# 05_-_CPU_-_PCIE_SATA.net
KiCad netlist of a schematic drawn in Altium Designer
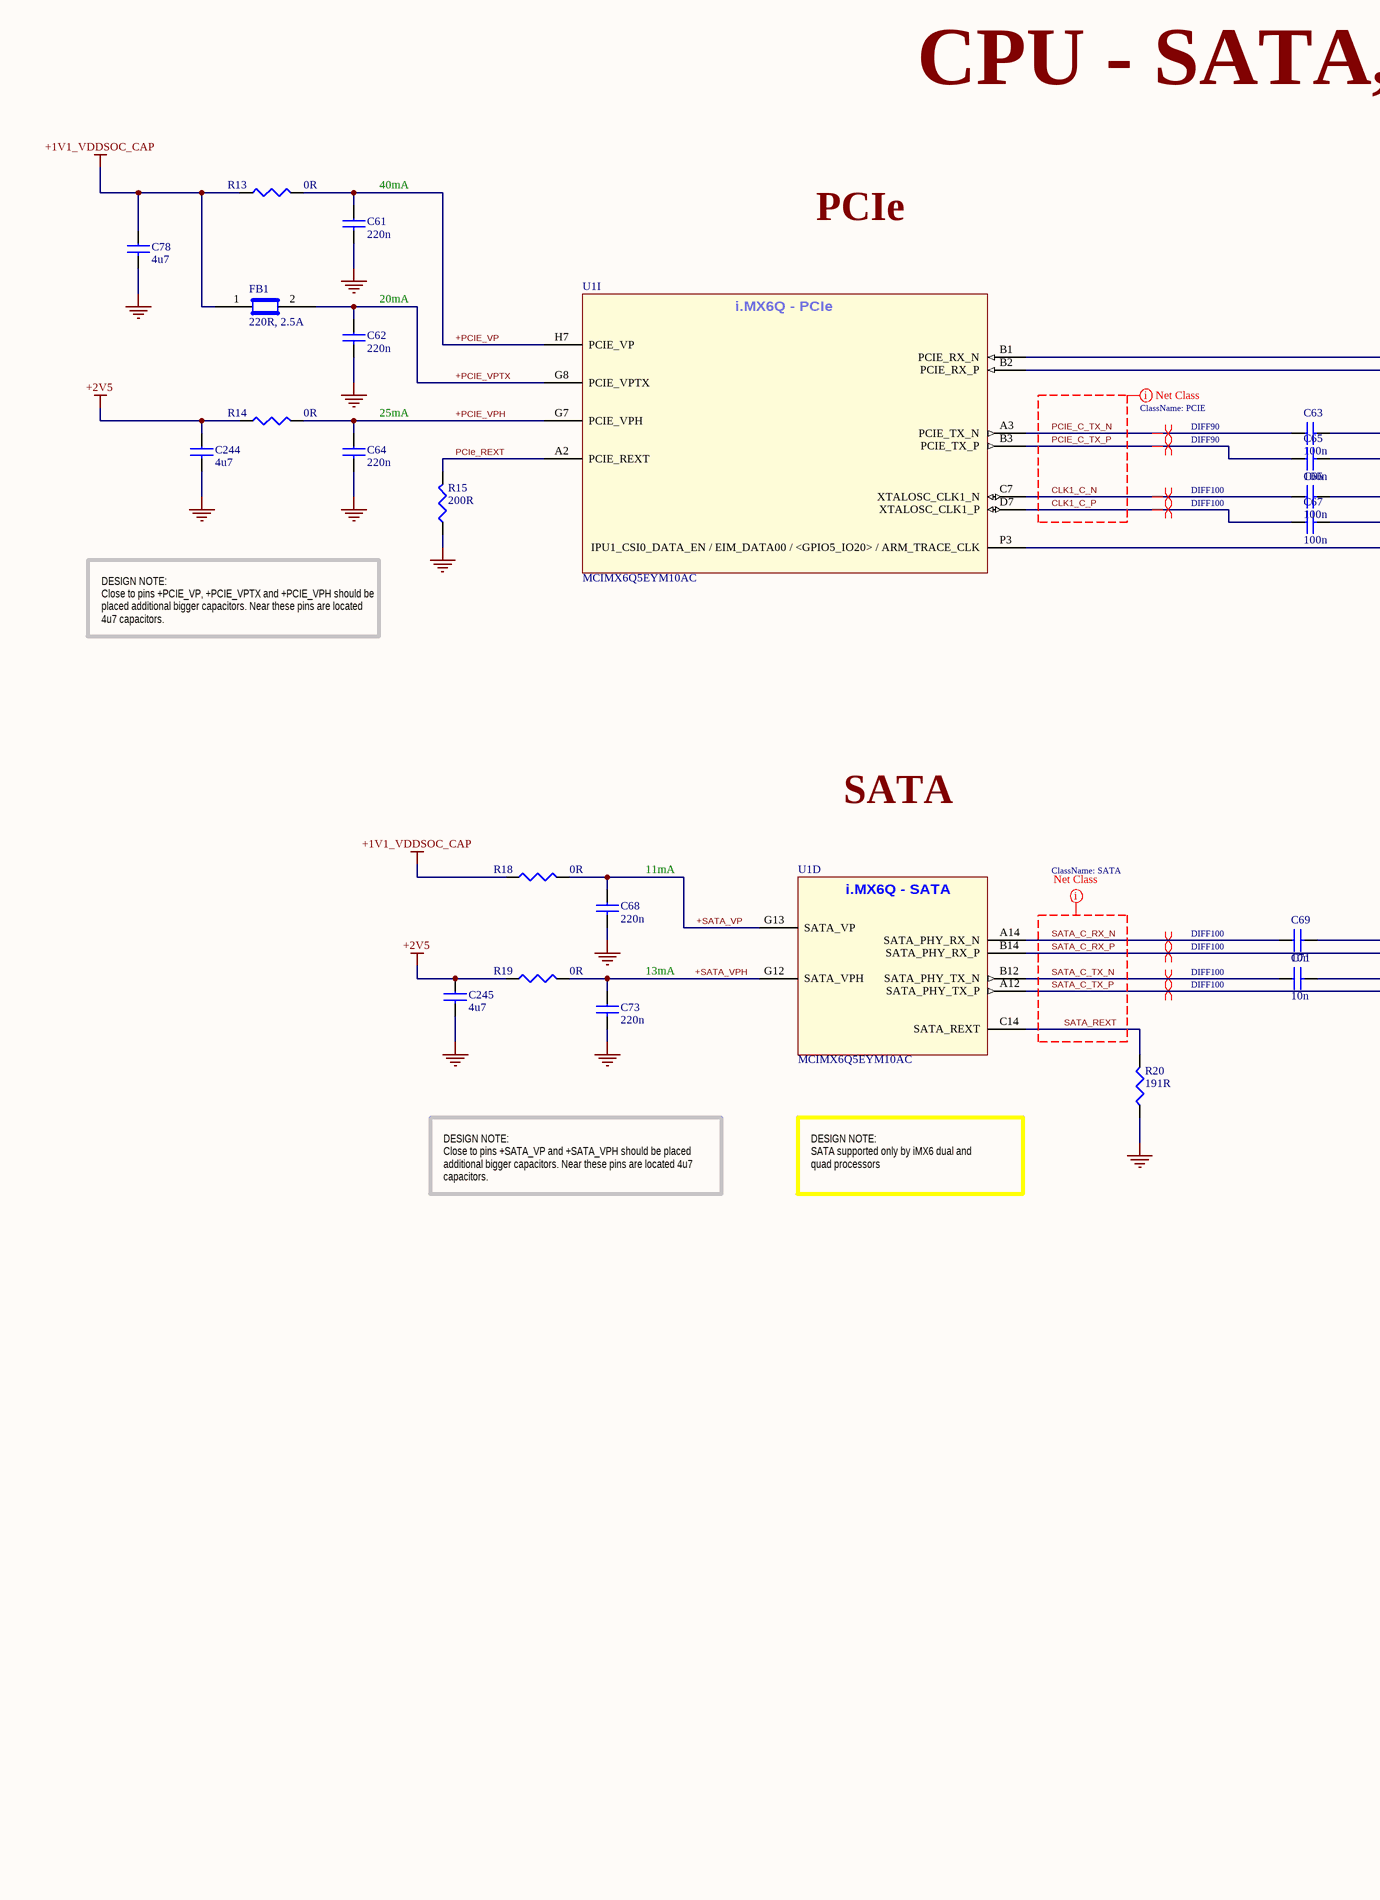
[diagram p0: [05] - CPU - PCIE, SATA.SchDoc, left]
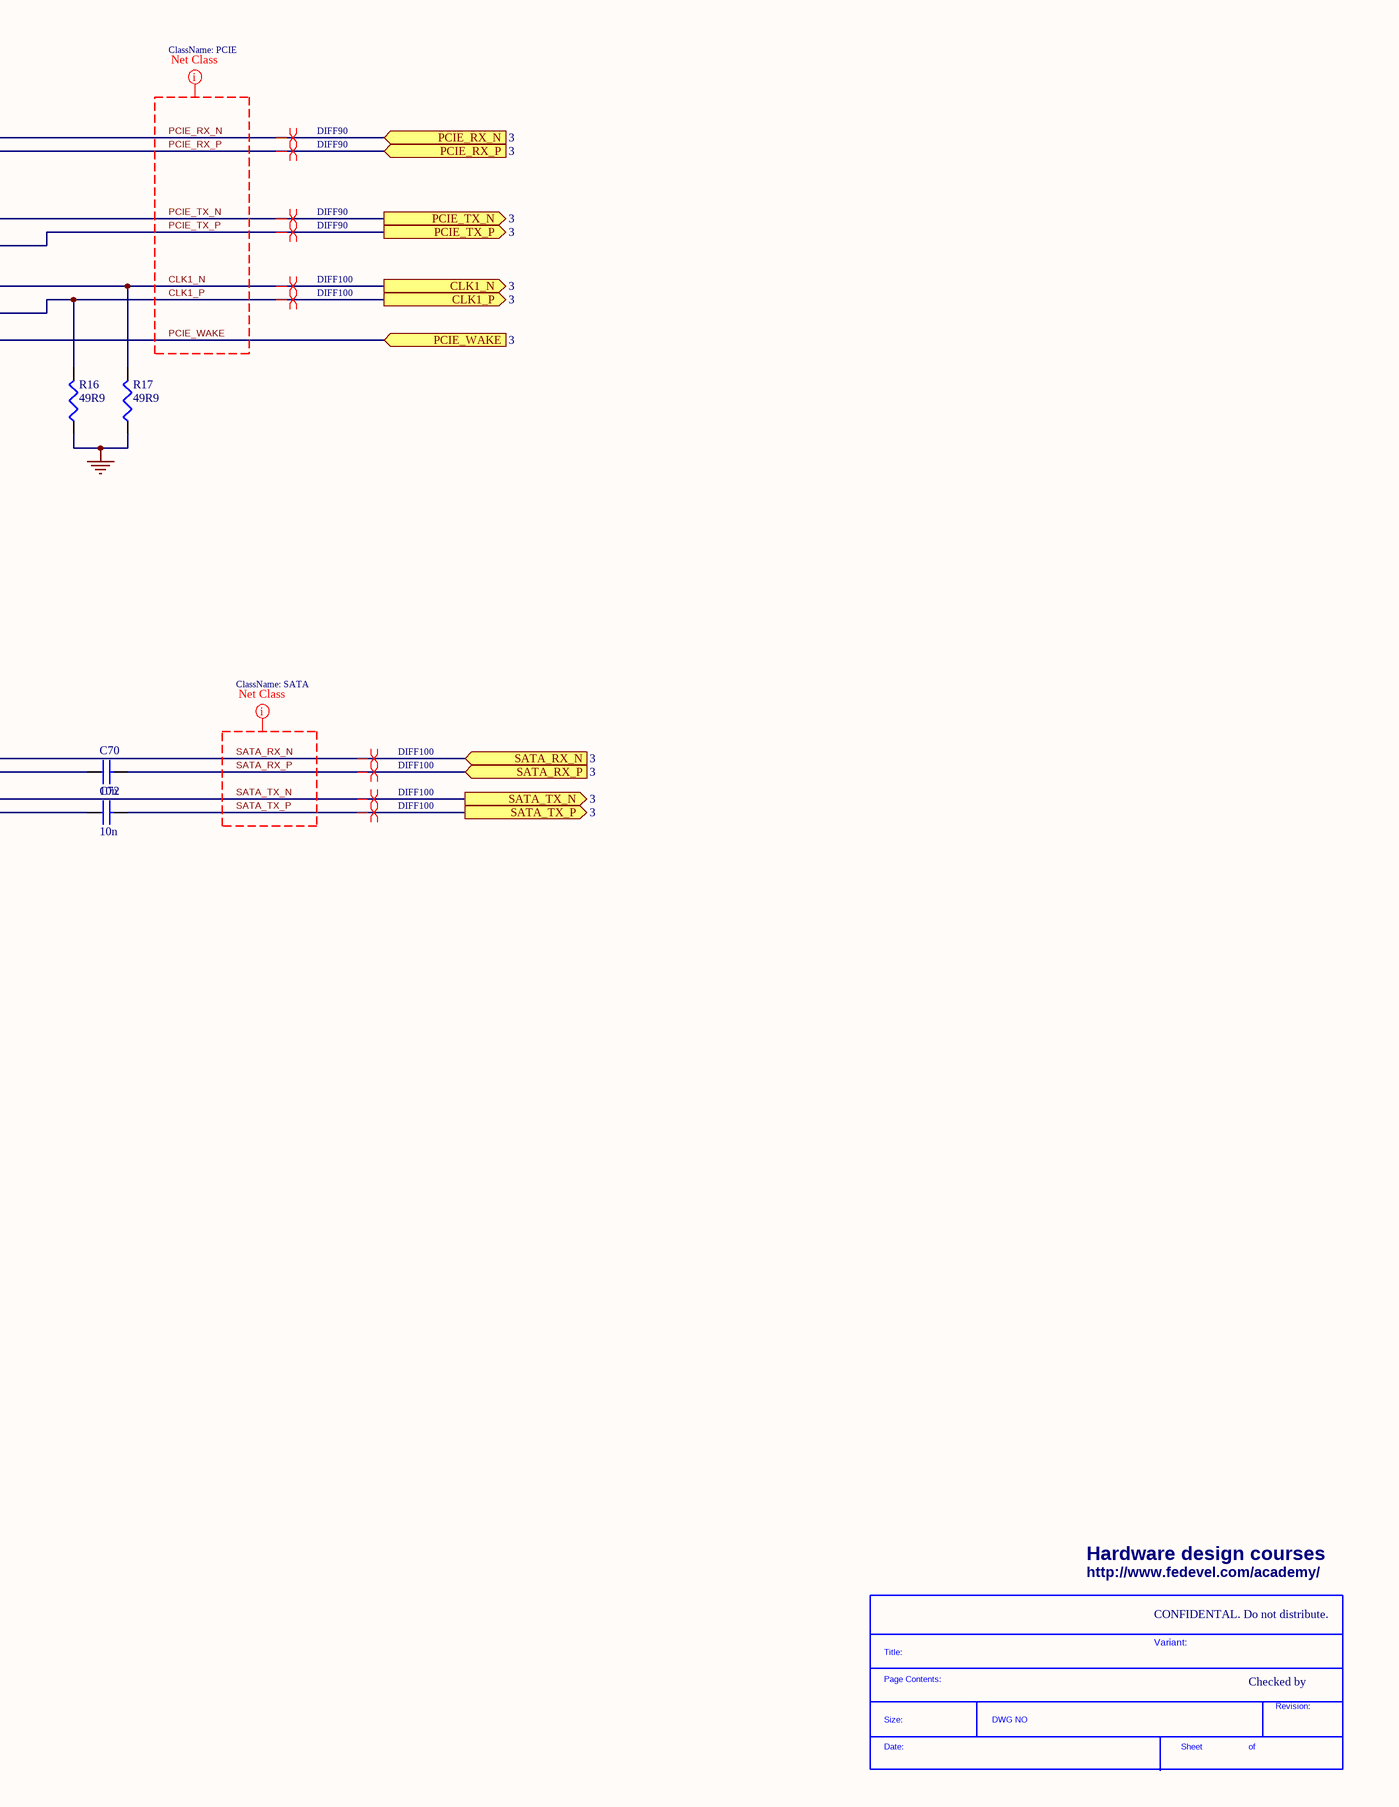
[diagram p1: [05] - CPU - PCIE, SATA.SchDoc, right]

(export (version "E")
  (design (tool "Eeschema 10.0.6"))
  (components
    (comp (ref "C61")
      (value "220n")
      (footprint "C0402")
      (description "CAP CER .22UF 25V X5R 20% 0402")
      (fields
        (field (name "MANUFACTURER") "TDK Corporation")
        (field (name "MANUFACTURER PART NUMBER") "C1005X5R1E224M")
      )
      (libsource (lib "iMX6 Rex_V1I1") (part "C1005X5R1E224M"))
    )
    (comp (ref "C62")
      (value "220n")
      (footprint "C0402")
      (description "CAP CER .22UF 25V X5R 20% 0402")
      (fields
        (field (name "MANUFACTURER") "TDK Corporation")
        (field (name "MANUFACTURER PART NUMBER") "C1005X5R1E224M")
      )
      (libsource (lib "iMX6 Rex_V1I1") (part "C1005X5R1E224M"))
    )
    (comp (ref "C63")
      (value "100n")
      (footprint "C0402")
      (description "CAP CER .10UF 50V X5R 10% 0402")
      (fields
        (field (name "MANUFACTURER") "TDK Corporation")
        (field (name "MANUFACTURER PART NUMBER") "C1005X5R1H104K")
      )
      (libsource (lib "iMX6 Rex_V1I1") (part "C1005X5R1H104K"))
    )
    (comp (ref "C64")
      (value "220n")
      (footprint "C0402")
      (description "CAP CER .22UF 25V X5R 20% 0402")
      (fields
        (field (name "MANUFACTURER") "TDK Corporation")
        (field (name "MANUFACTURER PART NUMBER") "C1005X5R1E224M")
      )
      (libsource (lib "iMX6 Rex_V1I1") (part "C1005X5R1E224M"))
    )
    (comp (ref "C65")
      (value "100n")
      (footprint "C0402")
      (description "CAP CER .10UF 50V X5R 10% 0402")
      (fields
        (field (name "MANUFACTURER") "TDK Corporation")
        (field (name "MANUFACTURER PART NUMBER") "C1005X5R1H104K")
      )
      (libsource (lib "iMX6 Rex_V1I1") (part "C1005X5R1H104K"))
    )
    (comp (ref "C66")
      (value "100n")
      (footprint "C0402")
      (description "CAP CER .10UF 50V X5R 10% 0402")
      (fields
        (field (name "MANUFACTURER") "TDK Corporation")
        (field (name "MANUFACTURER PART NUMBER") "C1005X5R1H104K")
      )
      (libsource (lib "iMX6 Rex_V1I1") (part "C1005X5R1H104K"))
    )
    (comp (ref "C67")
      (value "100n")
      (footprint "C0402")
      (description "CAP CER .10UF 50V X5R 10% 0402")
      (fields
        (field (name "MANUFACTURER") "TDK Corporation")
        (field (name "MANUFACTURER PART NUMBER") "C1005X5R1H104K")
      )
      (libsource (lib "iMX6 Rex_V1I1") (part "C1005X5R1H104K"))
    )
    (comp (ref "C68")
      (value "220n")
      (footprint "C0402")
      (description "CAP CER .22UF 25V X5R 20% 0402")
      (fields
        (field (name "MANUFACTURER") "TDK Corporation")
        (field (name "MANUFACTURER PART NUMBER") "C1005X5R1E224M")
      )
      (libsource (lib "iMX6 Rex_V1I1") (part "C1005X5R1E224M"))
    )
    (comp (ref "C69")
      (value "10n")
      (footprint "C0402")
      (description "CAP CER 10000PF 16V X7R 10% 0402")
      (fields
        (field (name "MANUFACTURER") "TDK Corporation")
        (field (name "MANUFACTURER PART NUMBER") "C1005X7R1C103K")
      )
      (libsource (lib "iMX6 Rex_V1I1") (part "C1005X7R1C103K"))
    )
    (comp (ref "C70")
      (value "10n")
      (footprint "C0402")
      (description "CAP CER 10000PF 16V X7R 10% 0402")
      (fields
        (field (name "MANUFACTURER") "TDK Corporation")
        (field (name "MANUFACTURER PART NUMBER") "C1005X7R1C103K")
      )
      (libsource (lib "iMX6 Rex_V1I1") (part "C1005X7R1C103K"))
    )
    (comp (ref "C71")
      (value "10n")
      (footprint "C0402")
      (description "CAP CER 10000PF 16V X7R 10% 0402")
      (fields
        (field (name "MANUFACTURER") "TDK Corporation")
        (field (name "MANUFACTURER PART NUMBER") "C1005X7R1C103K")
      )
      (libsource (lib "iMX6 Rex_V1I1") (part "C1005X7R1C103K"))
    )
    (comp (ref "C72")
      (value "10n")
      (footprint "C0402")
      (description "CAP CER 10000PF 16V X7R 10% 0402")
      (fields
        (field (name "MANUFACTURER") "TDK Corporation")
        (field (name "MANUFACTURER PART NUMBER") "C1005X7R1C103K")
      )
      (libsource (lib "iMX6 Rex_V1I1") (part "C1005X7R1C103K"))
    )
    (comp (ref "C73")
      (value "220n")
      (footprint "C0402")
      (description "CAP CER .22UF 25V X5R 20% 0402")
      (fields
        (field (name "MANUFACTURER") "TDK Corporation")
        (field (name "MANUFACTURER PART NUMBER") "C1005X5R1E224M")
      )
      (libsource (lib "iMX6 Rex_V1I1") (part "C1005X5R1E224M"))
    )
    (comp (ref "C78")
      (value "4u7")
      (footprint "C0402")
      (description "CAP CER 4.7UF 10V 20% X5R 0402")
      (fields
        (field (name "MANUFACTURER") "TDK Corporation")
        (field (name "MANUFACTURER PART NUMBER") "C1005X5R1A475M")
        (field (name ".CHECKED PCB") "RF")
        (field (name ".CHECKED SCH") "RF")
      )
      (libsource (lib "iMX6 Rex_V1I1") (part "C1005X5R1A475M"))
    )
    (comp (ref "C244")
      (value "4u7")
      (footprint "C0402")
      (description "CAP CER 4.7UF 10V 20% X5R 0402")
      (fields
        (field (name "MANUFACTURER") "TDK Corporation")
        (field (name "MANUFACTURER PART NUMBER") "C1005X5R1A475M")
        (field (name ".CHECKED PCB") "RF")
        (field (name ".CHECKED SCH") "RF")
      )
      (libsource (lib "iMX6 Rex_V1I1") (part "C1005X5R1A475M"))
    )
    (comp (ref "C245")
      (value "4u7")
      (footprint "C0402")
      (description "CAP CER 4.7UF 10V 20% X5R 0402")
      (fields
        (field (name "MANUFACTURER") "TDK Corporation")
        (field (name "MANUFACTURER PART NUMBER") "C1005X5R1A475M")
        (field (name ".CHECKED PCB") "RF")
        (field (name ".CHECKED SCH") "RF")
      )
      (libsource (lib "iMX6 Rex_V1I1") (part "C1005X5R1A475M"))
    )
    (comp (ref "FB1")
      (value "220R, 2.5A")
      (footprint "C0603")
      (description "FERRITE CHIP 220 OHM 2500MA 0603")
      (fields
        (field (name "MANUFACTURER") "Murata Electronics North America")
        (field (name "MANUFACTURER PART NUMBER") "BLM18SG221TN1D")
        (field (name ".CHECKED PCB") "RF")
        (field (name ".CHECKED SCH") "RF")
      )
      (libsource (lib "iMX6 Rex_V1I1") (part "BLM18SG221TN1D"))
    )
    (comp (ref "R13")
      (value "0R")
      (footprint "R0402")
      (description "RES 0.0 OHM 1/16W 0402 SMD")
      (fields
        (field (name "MANUFACTURER") "Yageo")
        (field (name "MANUFACTURER PART NUMBER") "RC0402JR-070RL")
      )
      (libsource (lib "iMX6 Rex_V1I1") (part "RC0402JR-070RL"))
    )
    (comp (ref "R14")
      (value "0R")
      (footprint "R0402")
      (description "RES 0.0 OHM 1/16W 0402 SMD")
      (fields
        (field (name "MANUFACTURER") "Yageo")
        (field (name "MANUFACTURER PART NUMBER") "RC0402JR-070RL")
      )
      (libsource (lib "iMX6 Rex_V1I1") (part "RC0402JR-070RL"))
    )
    (comp (ref "R15")
      (value "200R")
      (footprint "R0402")
      (description "RES 200 OHM 1/16W 1% 0402 SMD")
      (fields
        (field (name "MANUFACTURER") "Vishay Dale")
        (field (name "MANUFACTURER PART NUMBER") "CRCW0402200RFKED")
        (field (name ".CHECKED PCB") "RF, used by MM")
        (field (name ".CHECKED SCH") "MM, checked by RF")
        (field (name ".CREATOR") "MM")
      )
      (libsource (lib "iMX6 Rex_V1I1") (part "CRCW0402200RFKED"))
    )
    (comp (ref "R16")
      (value "49R9")
      (footprint "R0402")
      (description "RES 49.9 OHM 1/16W 1% 0402 SMD")
      (fields
        (field (name "MANUFACTURER") "Yageo")
        (field (name "MANUFACTURER PART NUMBER") "RC0402FR-0749R9L")
      )
      (libsource (lib "iMX6 Rex_V1I1") (part "RC0402FR-0749R9L"))
    )
    (comp (ref "R17")
      (value "49R9")
      (footprint "R0402")
      (description "RES 49.9 OHM 1/16W 1% 0402 SMD")
      (fields
        (field (name "MANUFACTURER") "Yageo")
        (field (name "MANUFACTURER PART NUMBER") "RC0402FR-0749R9L")
      )
      (libsource (lib "iMX6 Rex_V1I1") (part "RC0402FR-0749R9L"))
    )
    (comp (ref "R18")
      (value "0R")
      (footprint "R0402")
      (description "RES 0.0 OHM 1/16W 0402 SMD")
      (fields
        (field (name "MANUFACTURER") "Yageo")
        (field (name "MANUFACTURER PART NUMBER") "RC0402JR-070RL")
      )
      (libsource (lib "iMX6 Rex_V1I1") (part "RC0402JR-070RL"))
    )
    (comp (ref "R19")
      (value "0R")
      (footprint "R0402")
      (description "RES 0.0 OHM 1/16W 0402 SMD")
      (fields
        (field (name "MANUFACTURER") "Yageo")
        (field (name "MANUFACTURER PART NUMBER") "RC0402JR-070RL")
      )
      (libsource (lib "iMX6 Rex_V1I1") (part "RC0402JR-070RL"))
    )
    (comp (ref "R20")
      (value "191R")
      (footprint "R0402")
      (description "RES 191 OHM 1/16W 1% 0402 SMD")
      (fields
        (field (name "MANUFACTURER") "Vishay Dale")
        (field (name "MANUFACTURER PART NUMBER") "CRCW0402191RFKED")
        (field (name ".CREATOR") "MM")
        (field (name ".CHECKED PCB") "RF, used by MM")
        (field (name ".CHECKED SCH") "MM, checked by RF")
      )
      (libsource (lib "iMX6 Rex_V1I1") (part "CRCW0402191RFKED"))
    )
    (comp (ref "U1")
      (value "MCIMX6Q5EYM10AC")
      (footprint "PBGA624")
      (description "IC MCU 32BIT ARM QUAD 624FCBGA")
      (fields
        (field (name "MANUFACTURER") "Freescale Semiconductor")
        (field (name ".CREATOR") "MM")
        (field (name ".CHECKED PCB") "MM, checked by RF")
        (field (name ".CHECKED SCH") "MM")
      )
      (libsource (lib "iMX6 Rex_V1I1") (part "MCIMX6Q5EYM10AC"))
    )
  )
  (nets
    (net (code "1") (name "+1V1_VDDSOC_CAP") (class "Default")
      (node (ref "C78") (pin "1") (pinfunction "1_1") (pintype "passive"))
      (node (ref "FB1") (pin "1") (pinfunction "1_1") (pintype "passive"))
      (node (ref "R13") (pin "1") (pinfunction "1_1") (pintype "passive"))
      (node (ref "R18") (pin "1") (pinfunction "1_1") (pintype "passive"))
    )
    (net (code "2") (name "+2V5") (class "Default")
      (node (ref "C244") (pin "1") (pinfunction "1_1") (pintype "passive"))
      (node (ref "C245") (pin "1") (pinfunction "1_1") (pintype "passive"))
      (node (ref "R14") (pin "1") (pinfunction "1_1") (pintype "passive"))
      (node (ref "R19") (pin "1") (pinfunction "1_1") (pintype "passive"))
    )
    (net (code "3") (name "/+PCIE_VP") (class "Default")
      (node (ref "C61") (pin "1") (pinfunction "1_1") (pintype "passive"))
      (node (ref "R13") (pin "2") (pinfunction "2_2") (pintype "passive"))
      (node (ref "U1") (pin "H7") (pinfunction "PCIE_VP_H7") (pintype "power_in"))
    )
    (net (code "4") (name "/+PCIE_VPH") (class "Default")
      (node (ref "C64") (pin "1") (pinfunction "1_1") (pintype "passive"))
      (node (ref "R14") (pin "2") (pinfunction "2_2") (pintype "passive"))
      (node (ref "U1") (pin "G7") (pinfunction "PCIE_VPH_G7") (pintype "power_in"))
    )
    (net (code "5") (name "/+PCIE_VPTX") (class "Default")
      (node (ref "C62") (pin "1") (pinfunction "1_1") (pintype "passive"))
      (node (ref "FB1") (pin "2") (pinfunction "2_2") (pintype "passive"))
      (node (ref "U1") (pin "G8") (pinfunction "PCIE_VPTX_G8") (pintype "power_in"))
    )
    (net (code "6") (name "/+SATA_VP") (class "Default")
      (node (ref "C68") (pin "1") (pinfunction "1_1") (pintype "passive"))
      (node (ref "R18") (pin "2") (pinfunction "2_2") (pintype "passive"))
      (node (ref "U1") (pin "G13") (pinfunction "SATA_VP_G13") (pintype "power_in"))
    )
    (net (code "7") (name "/+SATA_VPH") (class "Default")
      (node (ref "C73") (pin "1") (pinfunction "1_1") (pintype "passive"))
      (node (ref "R19") (pin "2") (pinfunction "2_2") (pintype "passive"))
      (node (ref "U1") (pin "G12") (pinfunction "SATA_VPH_G12") (pintype "power_in"))
    )
    (net (code "8") (name "/CLK1_C_N") (class "Default")
      (node (ref "C66") (pin "1") (pinfunction "1_1") (pintype "passive"))
      (node (ref "U1") (pin "C7") (pinfunction "XTALOSC_CLK1_N_C7") (pintype "bidirectional"))
    )
    (net (code "9") (name "/CLK1_C_P") (class "Default")
      (node (ref "C67") (pin "1") (pinfunction "1_1") (pintype "passive"))
      (node (ref "U1") (pin "D7") (pinfunction "XTALOSC_CLK1_P_D7") (pintype "bidirectional"))
    )
    (net (code "10") (name "/CLK1_N") (class "Default")
      (node (ref "C66") (pin "2") (pinfunction "2_2") (pintype "passive"))
      (node (ref "R17") (pin "2") (pinfunction "2_2") (pintype "passive"))
    )
    (net (code "11") (name "/CLK1_P") (class "Default")
      (node (ref "C67") (pin "2") (pinfunction "2_2") (pintype "passive"))
      (node (ref "R16") (pin "2") (pinfunction "2_2") (pintype "passive"))
    )
    (net (code "12") (name "/PCIE_C_TX_N") (class "Default")
      (node (ref "C63") (pin "1") (pinfunction "1_1") (pintype "passive"))
      (node (ref "U1") (pin "A3") (pinfunction "PCIE_TX_N_A3") (pintype "output"))
    )
    (net (code "13") (name "/PCIE_C_TX_P") (class "Default")
      (node (ref "C65") (pin "1") (pinfunction "1_1") (pintype "passive"))
      (node (ref "U1") (pin "B3") (pinfunction "PCIE_TX_P_B3") (pintype "output"))
    )
    (net (code "14") (name "/PCIE_RX_N") (class "Default")
      (node (ref "U1") (pin "B1") (pinfunction "PCIE_RX_N_B1") (pintype "input"))
    )
    (net (code "15") (name "/PCIE_RX_P") (class "Default")
      (node (ref "U1") (pin "B2") (pinfunction "PCIE_RX_P_B2") (pintype "input"))
    )
    (net (code "16") (name "/PCIE_TX_N") (class "Default")
      (node (ref "C63") (pin "2") (pinfunction "2_2") (pintype "passive"))
    )
    (net (code "17") (name "/PCIE_TX_P") (class "Default")
      (node (ref "C65") (pin "2") (pinfunction "2_2") (pintype "passive"))
    )
    (net (code "18") (name "/PCIE_WAKE") (class "Default")
      (node (ref "U1") (pin "P3") (pinfunction "IPU1_CSI0_DATA_EN_/_EIM_DATA00_/_<GPIO5_IO20>_/_ARM_TRACE_CLK_P3") (pintype "passive"))
    )
    (net (code "19") (name "/PCIe_REXT") (class "Default")
      (node (ref "R15") (pin "2") (pinfunction "2_2") (pintype "passive"))
      (node (ref "U1") (pin "A2") (pinfunction "PCIE_REXT_A2") (pintype "passive"))
    )
    (net (code "20") (name "/SATA_C_RX_N") (class "Default")
      (node (ref "C69") (pin "1") (pinfunction "1_1") (pintype "passive"))
      (node (ref "U1") (pin "A14") (pinfunction "SATA_PHY_RX_N_A14") (pintype "passive"))
    )
    (net (code "21") (name "/SATA_C_RX_P") (class "Default")
      (node (ref "C70") (pin "1") (pinfunction "1_1") (pintype "passive"))
      (node (ref "U1") (pin "B14") (pinfunction "SATA_PHY_RX_P_B14") (pintype "passive"))
    )
    (net (code "22") (name "/SATA_C_TX_N") (class "Default")
      (node (ref "C71") (pin "1") (pinfunction "1_1") (pintype "passive"))
      (node (ref "U1") (pin "B12") (pinfunction "SATA_PHY_TX_N_B12") (pintype "output"))
    )
    (net (code "23") (name "/SATA_C_TX_P") (class "Default")
      (node (ref "C72") (pin "1") (pinfunction "1_1") (pintype "passive"))
      (node (ref "U1") (pin "A12") (pinfunction "SATA_PHY_TX_P_A12") (pintype "output"))
    )
    (net (code "24") (name "/SATA_REXT") (class "Default")
      (node (ref "R20") (pin "2") (pinfunction "2_2") (pintype "passive"))
      (node (ref "U1") (pin "C14") (pinfunction "SATA_REXT_C14") (pintype "passive"))
    )
    (net (code "25") (name "/SATA_RX_N") (class "Default")
      (node (ref "C69") (pin "2") (pinfunction "2_2") (pintype "passive"))
    )
    (net (code "26") (name "/SATA_RX_P") (class "Default")
      (node (ref "C70") (pin "2") (pinfunction "2_2") (pintype "passive"))
    )
    (net (code "27") (name "/SATA_TX_N") (class "Default")
      (node (ref "C71") (pin "2") (pinfunction "2_2") (pintype "passive"))
    )
    (net (code "28") (name "/SATA_TX_P") (class "Default")
      (node (ref "C72") (pin "2") (pinfunction "2_2") (pintype "passive"))
    )
    (net (code "29") (name "GND") (class "Default")
      (node (ref "C244") (pin "2") (pinfunction "2_2") (pintype "passive"))
      (node (ref "C245") (pin "2") (pinfunction "2_2") (pintype "passive"))
      (node (ref "C61") (pin "2") (pinfunction "2_2") (pintype "passive"))
      (node (ref "C62") (pin "2") (pinfunction "2_2") (pintype "passive"))
      (node (ref "C64") (pin "2") (pinfunction "2_2") (pintype "passive"))
      (node (ref "C68") (pin "2") (pinfunction "2_2") (pintype "passive"))
      (node (ref "C73") (pin "2") (pinfunction "2_2") (pintype "passive"))
      (node (ref "C78") (pin "2") (pinfunction "2_2") (pintype "passive"))
      (node (ref "R15") (pin "1") (pinfunction "1_1") (pintype "passive"))
      (node (ref "R16") (pin "1") (pinfunction "1_1") (pintype "passive"))
      (node (ref "R17") (pin "1") (pinfunction "1_1") (pintype "passive"))
      (node (ref "R20") (pin "1") (pinfunction "1_1") (pintype "passive"))
    )
  )
)
